# Current_Sensing.net
KiCad netlist of a schematic drawn in Altium Designer
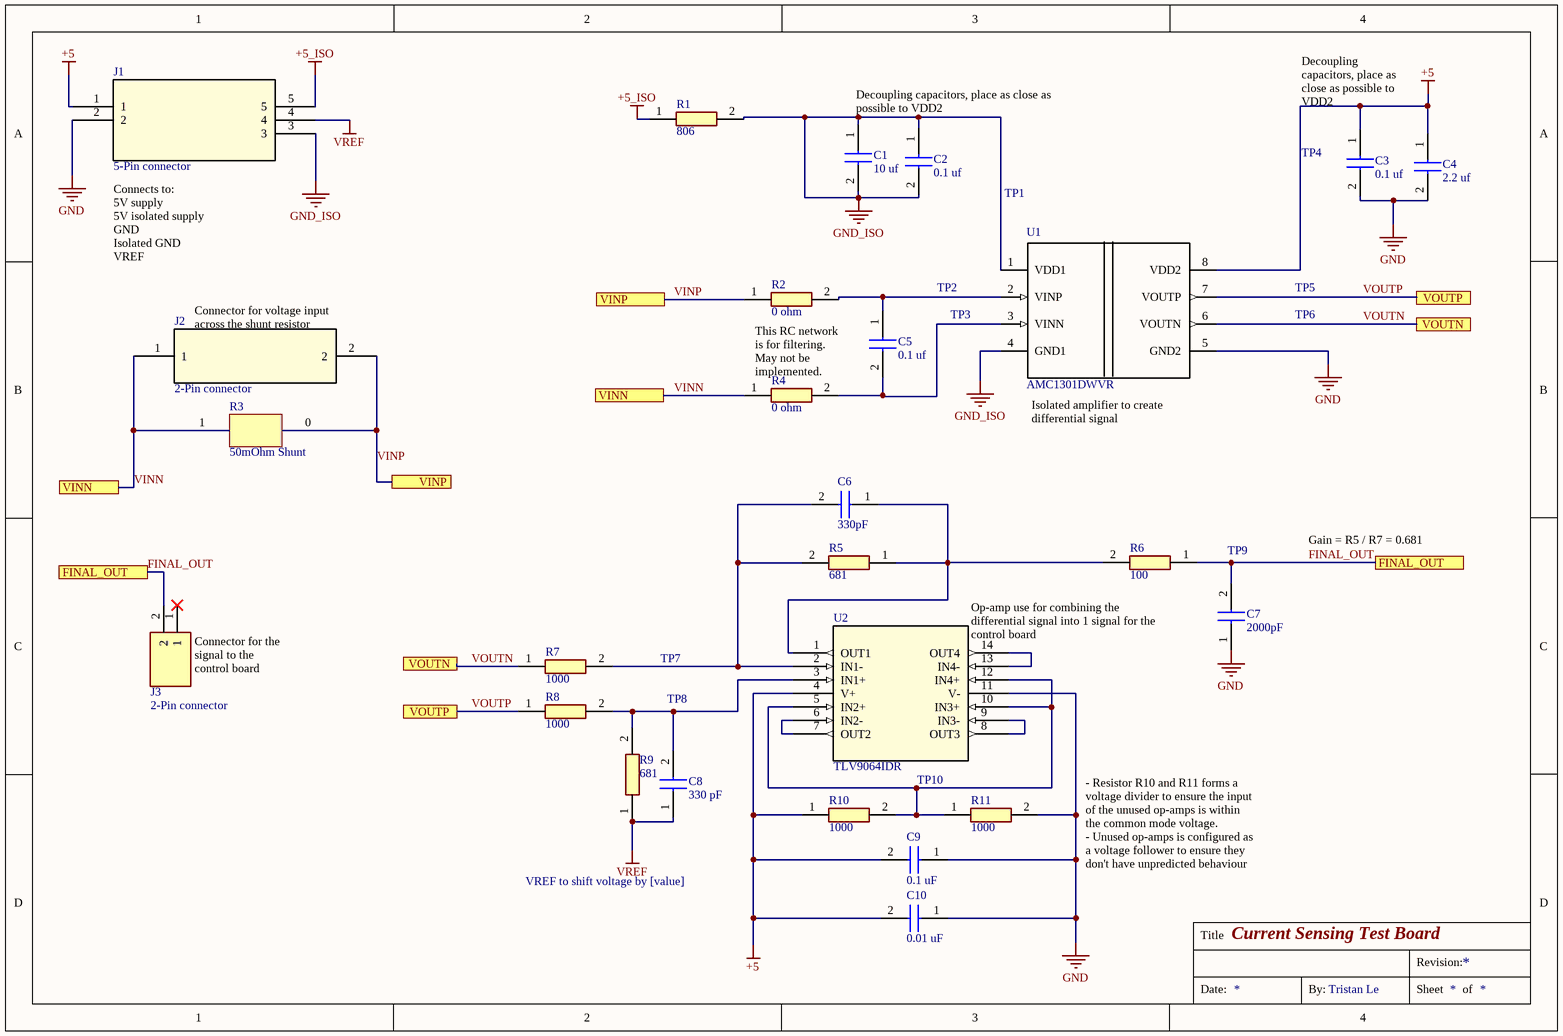
[diagram p0: Current Sensing.SchDoc]

(export (version "E")
  (design (tool "Eeschema 10.0.6"))
  (components
    (comp (ref "C1")
      (value "10 uf")
      (footprint "CC0805N")
      (description "Capacitor")
      (fields
        (field (name "MANUFACTURER_PART_NUMBER") "C0805C104K5RACTU")
        (field (name "MOUSER PART NUMBER") "80-C0805C104K5R")
      )
      (libsource (lib "SamacSys") (part "C0805C104K5RACTU"))
    )
    (comp (ref "C2")
      (value "0.1 uf")
      (footprint "CC0805N")
      (description "Capacitor")
      (fields
        (field (name "MANUFACTURER_PART_NUMBER") "C0805C104K5RACTU")
        (field (name "MOUSER PART NUMBER") "80-C0805C104K5R")
      )
      (libsource (lib "SamacSys") (part "C0805C104K5RACTU"))
    )
    (comp (ref "C3")
      (value "0.1 uf")
      (footprint "CC0805N")
      (description "Capacitor")
      (fields
        (field (name "MANUFACTURER_PART_NUMBER") "C0805C104K5RACTU")
        (field (name "MOUSER PART NUMBER") "80-C0805C104K5R")
      )
      (libsource (lib "SamacSys") (part "C0805C104K5RACTU"))
    )
    (comp (ref "C4")
      (value "2.2 uf")
      (footprint "CC0805N")
      (description "Capacitor")
      (fields
        (field (name "MANUFACTURER_PART_NUMBER") "C0805C104K5RACTU")
        (field (name "MOUSER PART NUMBER") "80-C0805C104K5R")
      )
      (libsource (lib "SamacSys") (part "C0805C104K5RACTU"))
    )
    (comp (ref "C5")
      (value "0.1 uf")
      (footprint "CC0805N")
      (description "Capacitor")
      (fields
        (field (name "MANUFACTURER_PART_NUMBER") "C0805C104K5RACTU")
        (field (name "MOUSER PART NUMBER") "80-C0805C104K5R")
      )
      (libsource (lib "SamacSys") (part "C0805C104K5RACTU"))
    )
    (comp (ref "C6")
      (value "330pF")
      (footprint "CC0805N")
      (description "Capacitor")
      (fields
        (field (name "MANUFACTURER_PART_NUMBER") "C0805C104K5RACTU")
        (field (name "MOUSER PART NUMBER") "80-C0805C104K5R")
      )
      (libsource (lib "SamacSys") (part "C0805C104K5RACTU"))
    )
    (comp (ref "C7")
      (value "2000pF")
      (footprint "CC0805N")
      (description "Capacitor")
      (fields
        (field (name "MANUFACTURER_PART_NUMBER") "C0805C104K5RACTU")
        (field (name "MOUSER PART NUMBER") "80-C0805C104K5R")
      )
      (libsource (lib "SamacSys") (part "C0805C104K5RACTU"))
    )
    (comp (ref "C8")
      (value "330 pF")
      (footprint "CC0805N")
      (description "Capacitor")
      (fields
        (field (name "MANUFACTURER_PART_NUMBER") "C0805C104K5RACTU")
        (field (name "MOUSER PART NUMBER") "80-C0805C104K5R")
      )
      (libsource (lib "SamacSys") (part "C0805C104K5RACTU"))
    )
    (comp (ref "C9")
      (value "0.1 uF")
      (footprint "CC0805N")
      (description "Capacitor")
      (fields
        (field (name "MANUFACTURER_PART_NUMBER") "C0805C104K5RACTU")
        (field (name "MOUSER PART NUMBER") "80-C0805C104K5R")
      )
      (libsource (lib "SamacSys") (part "C0805C104K5RACTU"))
    )
    (comp (ref "C10")
      (value "0.01 uF")
      (footprint "CC0805N")
      (description "Capacitor")
      (fields
        (field (name "MANUFACTURER_PART_NUMBER") "C0805C104K5RACTU")
        (field (name "MOUSER PART NUMBER") "80-C0805C104K5R")
      )
      (libsource (lib "SamacSys") (part "C0805C104K5RACTU"))
    )
    (comp (ref "J1")
      (value "5-Pin connector")
      (footprint "282836-5")
      (description "No Description Available")
      (fields
        (field (name "MANUFACTURER_PART_NUMBER") "282836-5")
        (field (name "COPYRIGHT") "Copyright (C) 2018 Accelerated Designs. All rights reserved")
      )
      (libsource (lib "TE_AMP_Connector_282836-5Pins") (part "282836-5"))
    )
    (comp (ref "J2")
      (value "2-Pin connector")
      (footprint "282837-2")
      (description "No Description Available")
      (fields
        (field (name "MANUFACTURER_PART_NUMBER") "282837-2")
        (field (name "COPYRIGHT") "Copyright (C) 2018 Accelerated Designs. All rights reserved")
      )
      (libsource (lib "TI_AMP_Connector_282837-2") (part "282837-2"))
    )
    (comp (ref "J3")
      (value "2-Pin connector")
      (footprint "SHDR2W64P0X250_1X2_740X575X700P")
      (description "Connector")
      (fields (field (name "MANUFACTURER_PART_NUMBER") "B2B-XH-A(LF)(SN)"))
      (libsource (lib "SamacSys") (part "B2B-XH-A(LF)(SN)"))
    )
    (comp (ref "R1")
      (value "806")
      (footprint "SamacSys:RESC0603X26N")
      (description "Resistor")
      (fields
        (field (name "MANUFACTURER_PART_NUMBER") "RC0201JR-0710RL")
        (field (name "MOUSER PART NUMBER") "603-RC0201JR-0710RL")
      )
      (libsource (lib "SamacSys") (part "RC0201JR-0710RL"))
    )
    (comp (ref "R2")
      (value "0 ohm")
      (footprint "SamacSys:RESC0603X26N")
      (description "Resistor")
      (fields
        (field (name "MANUFACTURER_PART_NUMBER") "RC0201JR-0710RL")
        (field (name "MOUSER PART NUMBER") "603-RC0201JR-0710RL")
      )
      (libsource (lib "SamacSys") (part "RC0201JR-0710RL"))
    )
    (comp (ref "R3")
      (value "50mOhm Shunt")
      (footprint "R_Shunt")
      (description "50 mOhms ±1% 10W Chip Resistor")
      (libsource (lib "Schlib") (part "R_SHUNT"))
    )
    (comp (ref "R4")
      (value "0 ohm")
      (footprint "RESC0603X26N")
      (description "Resistor")
      (fields
        (field (name "MANUFACTURER_PART_NUMBER") "RC0201JR-0710RL")
        (field (name "MOUSER PART NUMBER") "603-RC0201JR-0710RL")
      )
      (libsource (lib "SamacSys") (part "RC0201JR-0710RL"))
    )
    (comp (ref "R5")
      (value "681")
      (footprint "RESC0603X26N")
      (description "Resistor")
      (fields
        (field (name "MANUFACTURER_PART_NUMBER") "RC0201JR-0710RL")
        (field (name "MOUSER PART NUMBER") "603-RC0201JR-0710RL")
      )
      (libsource (lib "") (part "RC0201JR-0710RL_1"))
    )
    (comp (ref "R6")
      (value "100")
      (footprint "RESC0603X26N")
      (description "Resistor")
      (fields
        (field (name "MANUFACTURER_PART_NUMBER") "RC0201JR-0710RL")
        (field (name "MOUSER PART NUMBER") "603-RC0201JR-0710RL")
      )
      (libsource (lib "") (part "RC0201JR-0710RL_1"))
    )
    (comp (ref "R7")
      (value "1000")
      (footprint "RESC0603X26N")
      (description "Resistor")
      (fields
        (field (name "MANUFACTURER_PART_NUMBER") "RC0201JR-0710RL")
        (field (name "MOUSER PART NUMBER") "603-RC0201JR-0710RL")
      )
      (libsource (lib "SamacSys") (part "RC0201JR-0710RL"))
    )
    (comp (ref "R8")
      (value "1000")
      (footprint "RESC0603X26N")
      (description "Resistor")
      (fields
        (field (name "MANUFACTURER_PART_NUMBER") "RC0201JR-0710RL")
        (field (name "MOUSER PART NUMBER") "603-RC0201JR-0710RL")
      )
      (libsource (lib "SamacSys") (part "RC0201JR-0710RL"))
    )
    (comp (ref "R9")
      (value "681")
      (footprint "RESC0603X26N")
      (description "Resistor")
      (fields
        (field (name "MANUFACTURER_PART_NUMBER") "RC0201JR-0710RL")
        (field (name "MOUSER PART NUMBER") "603-RC0201JR-0710RL")
      )
      (libsource (lib "") (part "RC0201JR-0710RL_2"))
    )
    (comp (ref "R10")
      (value "1000")
      (footprint "RESC0603X26N")
      (description "Resistor")
      (fields
        (field (name "MANUFACTURER_PART_NUMBER") "RC0201JR-0710RL")
        (field (name "MOUSER PART NUMBER") "603-RC0201JR-0710RL")
      )
      (libsource (lib "SamacSys") (part "RC0201JR-0710RL"))
    )
    (comp (ref "R11")
      (value "1000")
      (footprint "RESC0603X26N")
      (description "Resistor")
      (fields
        (field (name "MANUFACTURER_PART_NUMBER") "RC0201JR-0710RL")
        (field (name "MOUSER PART NUMBER") "603-RC0201JR-0710RL")
      )
      (libsource (lib "SamacSys") (part "RC0201JR-0710RL"))
    )
    (comp (ref "U1")
      (value "AMC1301DWVR")
      (footprint "DWV0008A")
      (description "No Description Available")
      (fields (field (name "COPYRIGHT") "Copyright (C) 2018 Accelerated Designs. All rights reserved"))
      (libsource (lib "2019-10-25_01-05-10") (part "AMC1301DWVR"))
    )
    (comp (ref "U2")
      (value "TLV9064IDR")
      (footprint "D14")
      (description "No Description Available")
      (fields (field (name "COPYRIGHT") "Copyright (C) 2016 Accelerated Designs. All rights reserved"))
      (libsource (lib "2019-11-02_14-15-07") (part "TLV9064IDR"))
    )
  )
  (nets
    (net (code "1") (name "+5") (class "Default")
      (node (ref "C10") (pin "2") (pinfunction "2_2") (pintype "passive"))
      (node (ref "C3") (pin "1") (pinfunction "1_1") (pintype "passive"))
      (node (ref "C4") (pin "1") (pinfunction "1_1") (pintype "passive"))
      (node (ref "C9") (pin "2") (pinfunction "2_2") (pintype "passive"))
      (node (ref "J1") (pin "1") (pinfunction "1_1") (pintype "passive"))
      (node (ref "R10") (pin "1") (pinfunction "1_1") (pintype "passive"))
      (node (ref "U1") (pin "8") (pinfunction "VDD2_8") (pintype "power_in"))
      (node (ref "U2") (pin "4") (pinfunction "V+_4") (pintype "power_in"))
    )
    (net (code "2") (name "+5_ISO") (class "Default")
      (node (ref "J1") (pin "5") (pinfunction "5_5") (pintype "passive"))
      (node (ref "R1") (pin "1") (pinfunction "1_1") (pintype "passive"))
    )
    (net (code "3") (name "/FINAL_OUT") (class "Default")
      (node (ref "C7") (pin "2") (pinfunction "2_2") (pintype "passive"))
      (node (ref "J3") (pin "2") (pinfunction "2_2") (pintype "passive"))
      (node (ref "R6") (pin "1") (pinfunction "1_1") (pintype "passive"))
    )
    (net (code "4") (name "/VINN") (class "Default")
      (node (ref "J2") (pin "1") (pinfunction "1_1") (pintype "passive"))
      (node (ref "R3") (pin "1") (pintype "passive"))
      (node (ref "R4") (pin "1") (pinfunction "1_1") (pintype "passive"))
    )
    (net (code "5") (name "/VINP") (class "Default")
      (node (ref "J2") (pin "2") (pinfunction "2_2") (pintype "passive"))
      (node (ref "R2") (pin "1") (pinfunction "1_1") (pintype "passive"))
      (node (ref "R3") (pin "0") (pintype "passive"))
    )
    (net (code "6") (name "/VOUTN") (class "Default")
      (node (ref "R7") (pin "1") (pinfunction "1_1") (pintype "passive"))
      (node (ref "U1") (pin "6") (pinfunction "VOUTN_6") (pintype "output"))
    )
    (net (code "7") (name "/VOUTP") (class "Default")
      (node (ref "R8") (pin "1") (pinfunction "1_1") (pintype "passive"))
      (node (ref "U1") (pin "7") (pinfunction "VOUTP_7") (pintype "output"))
    )
    (net (code "8") (name "GND") (class "Default")
      (node (ref "C10") (pin "1") (pinfunction "1_1") (pintype "passive"))
      (node (ref "C3") (pin "2") (pinfunction "2_2") (pintype "passive"))
      (node (ref "C4") (pin "2") (pinfunction "2_2") (pintype "passive"))
      (node (ref "C7") (pin "1") (pinfunction "1_1") (pintype "passive"))
      (node (ref "C9") (pin "1") (pinfunction "1_1") (pintype "passive"))
      (node (ref "J1") (pin "2") (pinfunction "2_2") (pintype "passive"))
      (node (ref "R11") (pin "2") (pinfunction "2_2") (pintype "passive"))
      (node (ref "U1") (pin "5") (pinfunction "GND2_5") (pintype "power_in"))
      (node (ref "U2") (pin "11") (pinfunction "V-_11") (pintype "power_in"))
    )
    (net (code "9") (name "GND_ISO") (class "Default")
      (node (ref "C1") (pin "1") (pinfunction "1_1") (pintype "passive"))
      (node (ref "C1") (pin "2") (pinfunction "2_2") (pintype "passive"))
      (node (ref "C2") (pin "1") (pinfunction "1_1") (pintype "passive"))
      (node (ref "C2") (pin "2") (pinfunction "2_2") (pintype "passive"))
      (node (ref "J1") (pin "3") (pinfunction "3_3") (pintype "passive"))
      (node (ref "R1") (pin "2") (pinfunction "2_2") (pintype "passive"))
      (node (ref "U1") (pin "1") (pinfunction "VDD1_1") (pintype "power_in"))
      (node (ref "U1") (pin "4") (pinfunction "GND1_4") (pintype "power_in"))
    )
    (net (code "10") (name "Net-(U1-VINN)") (class "Default")
      (node (ref "C5") (pin "2") (pinfunction "2_2") (pintype "passive"))
      (node (ref "R4") (pin "2") (pinfunction "2_2") (pintype "passive"))
      (node (ref "U1") (pin "3") (pinfunction "VINN_3") (pintype "input"))
    )
    (net (code "11") (name "Net-(U1-VINP)") (class "Default")
      (node (ref "C5") (pin "1") (pinfunction "1_1") (pintype "passive"))
      (node (ref "R2") (pin "2") (pinfunction "2_2") (pintype "passive"))
      (node (ref "U1") (pin "2") (pinfunction "VINP_2") (pintype "input"))
    )
    (net (code "12") (name "Net-(U2-IN1+)") (class "Default")
      (node (ref "C8") (pin "2") (pinfunction "2_2") (pintype "passive"))
      (node (ref "R8") (pin "2") (pinfunction "2_2") (pintype "passive"))
      (node (ref "R9") (pin "2") (pinfunction "2_2") (pintype "passive"))
      (node (ref "U2") (pin "3") (pinfunction "IN1+_3") (pintype "input"))
    )
    (net (code "13") (name "Net-(U2-IN1-)") (class "Default")
      (node (ref "C6") (pin "2") (pinfunction "2_2") (pintype "passive"))
      (node (ref "R5") (pin "2") (pinfunction "2_2") (pintype "passive"))
      (node (ref "R7") (pin "2") (pinfunction "2_2") (pintype "passive"))
      (node (ref "U2") (pin "2") (pinfunction "IN1-_2") (pintype "input"))
    )
    (net (code "14") (name "Net-(U2-IN2+)") (class "Default")
      (node (ref "R10") (pin "2") (pinfunction "2_2") (pintype "passive"))
      (node (ref "R11") (pin "1") (pinfunction "1_1") (pintype "passive"))
      (node (ref "U2") (pin "10") (pinfunction "IN3+_10") (pintype "input"))
      (node (ref "U2") (pin "12") (pinfunction "IN4+_12") (pintype "input"))
      (node (ref "U2") (pin "5") (pinfunction "IN2+_5") (pintype "input"))
    )
    (net (code "15") (name "Net-(U2-IN2-)") (class "Default")
      (node (ref "U2") (pin "6") (pinfunction "IN2-_6") (pintype "input"))
      (node (ref "U2") (pin "7") (pinfunction "OUT2_7") (pintype "output"))
    )
    (net (code "16") (name "Net-(U2-IN3-)") (class "Default")
      (node (ref "U2") (pin "8") (pinfunction "OUT3_8") (pintype "output"))
      (node (ref "U2") (pin "9") (pinfunction "IN3-_9") (pintype "input"))
    )
    (net (code "17") (name "Net-(U2-IN4-)") (class "Default")
      (node (ref "U2") (pin "13") (pinfunction "IN4-_13") (pintype "input"))
      (node (ref "U2") (pin "14") (pinfunction "OUT4_14") (pintype "output"))
    )
    (net (code "18") (name "Net-(U2-OUT1)") (class "Default")
      (node (ref "C6") (pin "1") (pinfunction "1_1") (pintype "passive"))
      (node (ref "R5") (pin "1") (pinfunction "1_1") (pintype "passive"))
      (node (ref "R6") (pin "2") (pinfunction "2_2") (pintype "passive"))
      (node (ref "U2") (pin "1") (pinfunction "OUT1_1") (pintype "output"))
    )
    (net (code "19") (name "VREF") (class "Default")
      (node (ref "C8") (pin "1") (pinfunction "1_1") (pintype "passive"))
      (node (ref "J1") (pin "4") (pinfunction "4_4") (pintype "passive"))
      (node (ref "R9") (pin "1") (pinfunction "1_1") (pintype "passive"))
    )
    (net (code "20") (name "unconnected-(J3-Pad1)") (class "Default")
      (node (ref "J3") (pin "1") (pinfunction "1_1") (pintype "passive+no_connect"))
    )
  )
)
